# TRV_MRF49_V1_2.net
KiCad netlist of a schematic drawn in EAGLE
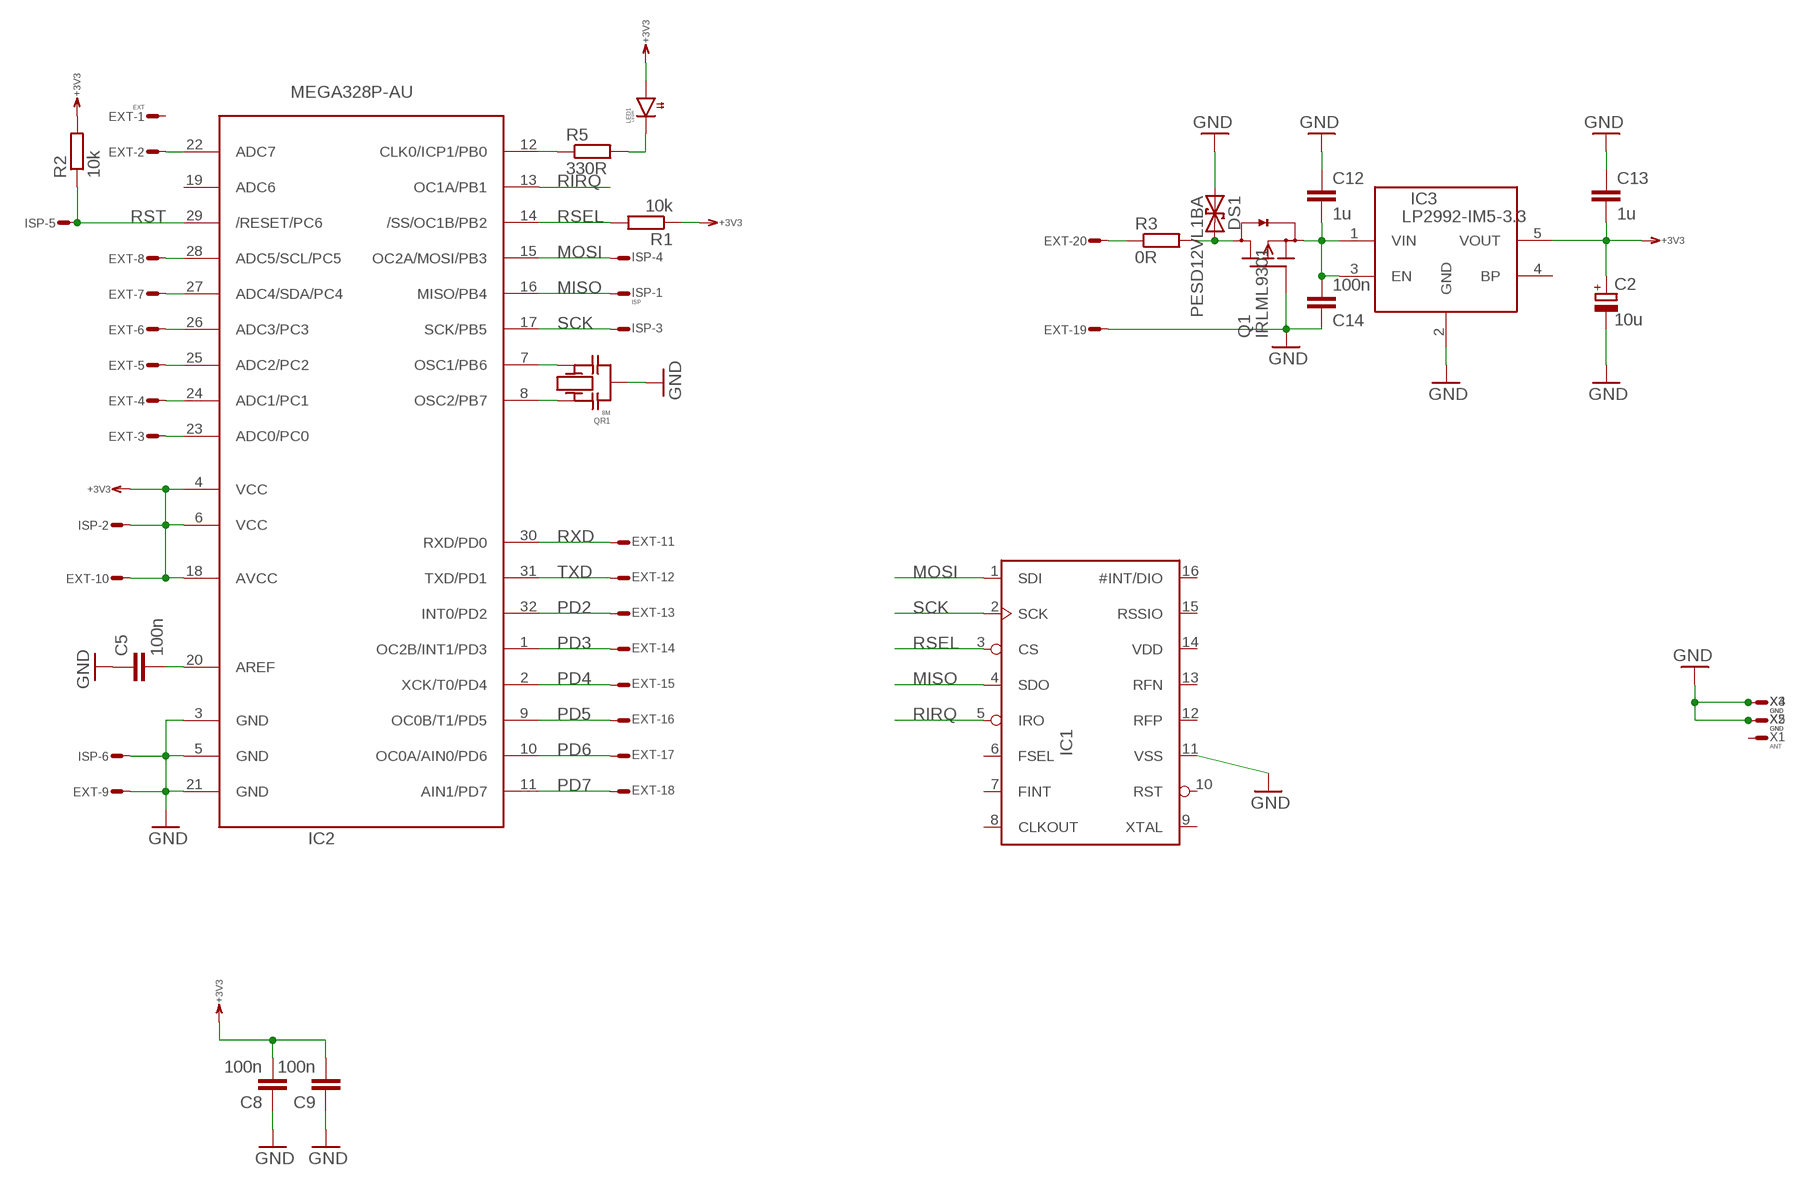
[diagram p0: schematic, sheet 1]

(export (version "E")
  (design (tool "Eeschema 10.0.6"))
  (components
    (comp (ref "C2")
      (value "10u")
      (footprint "eagle-import:SMC_B")
      (libsource (lib "eagle-import") (part "C_POLSMCB"))
    )
    (comp (ref "C5")
      (value "100n")
      (footprint "eagle-import:0603")
      (libsource (lib "eagle-import") (part "C0603"))
    )
    (comp (ref "C8")
      (value "100n")
      (footprint "eagle-import:0603")
      (libsource (lib "eagle-import") (part "C0603"))
    )
    (comp (ref "C9")
      (value "100n")
      (footprint "eagle-import:0603")
      (libsource (lib "eagle-import") (part "C0603"))
    )
    (comp (ref "C12")
      (value "1u")
      (footprint "eagle-import:0603")
      (libsource (lib "eagle-import") (part "C0603"))
    )
    (comp (ref "C13")
      (value "1u")
      (footprint "eagle-import:0603")
      (libsource (lib "eagle-import") (part "C0603"))
    )
    (comp (ref "C14")
      (value "100n")
      (footprint "eagle-import:0603")
      (libsource (lib "eagle-import") (part "C0603"))
    )
    (comp (ref "DS1")
      (value "PESD12VL1BA")
      (footprint "eagle-import:SOD323")
      (libsource (lib "eagle-import") (part "TVS-U323"))
    )
    (comp (ref "EXT")
      (value "EXT")
      (footprint "eagle-import:ML20S")
      (libsource (lib "eagle-import") (part "ML20?ES"))
    )
    (comp (ref "IC1")
      (value "MRF49XA")
      (footprint "eagle-import:TSSOP16")
      (libsource (lib "eagle-import") (part "MRF49XA"))
    )
    (comp (ref "IC2")
      (value "MEGA328P-AU")
      (footprint "eagle-import:TQFP32-08")
      (libsource (lib "eagle-import") (part "MEGA168PA"))
    )
    (comp (ref "IC3")
      (value "LP2992-IM5-3.3")
      (footprint "eagle-import:SOT23-5")
      (libsource (lib "eagle-import") (part "LDO"))
    )
    (comp (ref "ISP")
      (value "ISP")
      (footprint "eagle-import:ML6S")
      (libsource (lib "eagle-import") (part "ML6ES"))
    )
    (comp (ref "LED1")
      (value "LEDR")
      (footprint "eagle-import:0805")
      (libsource (lib "eagle-import") (part "LED0805"))
    )
    (comp (ref "Q1")
      (value "IRLML9301")
      (footprint "eagle-import:SOT23")
      (libsource (lib "eagle-import") (part "FET-PDSOT23"))
    )
    (comp (ref "QR1")
      (value "8M")
      (footprint "eagle-import:CR")
      (libsource (lib "eagle-import") (part "QRCR"))
    )
    (comp (ref "R1")
      (value "10k")
      (footprint "eagle-import:0603")
      (libsource (lib "eagle-import") (part "R0603"))
    )
    (comp (ref "R2")
      (value "10k")
      (footprint "eagle-import:0603")
      (libsource (lib "eagle-import") (part "R0603"))
    )
    (comp (ref "R3")
      (value "0R")
      (footprint "eagle-import:0603")
      (libsource (lib "eagle-import") (part "R0603"))
    )
    (comp (ref "R5")
      (value "330R")
      (footprint "eagle-import:0603")
      (libsource (lib "eagle-import") (part "R0603"))
    )
    (comp (ref "X1")
      (value "ANT")
      (footprint "eagle-import:S2.54_1.27")
      (libsource (lib "eagle-import") (part "WIREPADS2.54/1.27"))
    )
    (comp (ref "X2")
      (value "GND")
      (footprint "eagle-import:S2.54_1.27")
      (libsource (lib "eagle-import") (part "WIREPADS2.54/1.27"))
    )
    (comp (ref "X3")
      (value "GND")
      (footprint "eagle-import:S2.54_1.27")
      (libsource (lib "eagle-import") (part "WIREPADS2.54/1.27"))
    )
    (comp (ref "X4")
      (value "GND")
      (footprint "eagle-import:S2.54_1.27")
      (libsource (lib "eagle-import") (part "WIREPADS2.54/1.27"))
    )
    (comp (ref "X5")
      (value "GND")
      (footprint "eagle-import:S2.54_1.27")
      (libsource (lib "eagle-import") (part "WIREPADS2.54/1.27"))
    )
  )
  (nets
    (net (code "1") (name "+3V3") (class "Default")
      (node (ref "C13") (pin "2") (pinfunction "2_2") (pintype "passive"))
      (node (ref "C2") (pin "+") (pinfunction "+_+") (pintype "passive"))
      (node (ref "C8") (pin "2") (pinfunction "2_2") (pintype "passive"))
      (node (ref "C9") (pin "2") (pinfunction "2_2") (pintype "passive"))
      (node (ref "EXT") (pin "10") (pinfunction "S_10") (pintype "passive"))
      (node (ref "IC2") (pin "18") (pinfunction "AVCC_18") (pintype "bidirectional"))
      (node (ref "IC2") (pin "4") (pinfunction "VCC_4") (pintype "bidirectional"))
      (node (ref "IC2") (pin "6") (pinfunction "VCC_6") (pintype "bidirectional"))
      (node (ref "IC3") (pin "5") (pinfunction "VOUT_5") (pintype "bidirectional"))
      (node (ref "ISP") (pin "2") (pinfunction "S_2") (pintype "passive"))
      (node (ref "LED1") (pin "C") (pinfunction "A_C") (pintype "bidirectional"))
      (node (ref "R1") (pin "1") (pinfunction "1_1") (pintype "passive"))
      (node (ref "R2") (pin "2") (pinfunction "2_2") (pintype "passive"))
    )
    (net (code "2") (name "/MISO") (class "Default")
      (node (ref "IC1") (pin "4") (pinfunction "SDO_4") (pintype "output"))
      (node (ref "IC2") (pin "16") (pinfunction "MISO/PB4_16") (pintype "bidirectional"))
      (node (ref "ISP") (pin "1") (pinfunction "S_1") (pintype "passive"))
    )
    (net (code "3") (name "/MOSI") (class "Default")
      (node (ref "IC1") (pin "1") (pinfunction "SDI_1") (pintype "input"))
      (node (ref "IC2") (pin "15") (pinfunction "OC2A/MOSI/PB3_15") (pintype "bidirectional"))
      (node (ref "ISP") (pin "4") (pinfunction "S_4") (pintype "passive"))
    )
    (net (code "4") (name "/PD2") (class "Default")
      (node (ref "EXT") (pin "13") (pinfunction "S_13") (pintype "passive"))
      (node (ref "IC2") (pin "32") (pinfunction "INT0/PD2_32") (pintype "bidirectional"))
    )
    (net (code "5") (name "/PD3") (class "Default")
      (node (ref "EXT") (pin "14") (pinfunction "S_14") (pintype "passive"))
      (node (ref "IC2") (pin "1") (pinfunction "OC2B/INT1/PD3_1") (pintype "bidirectional"))
    )
    (net (code "6") (name "/PD4") (class "Default")
      (node (ref "EXT") (pin "15") (pinfunction "S_15") (pintype "passive"))
      (node (ref "IC2") (pin "2") (pinfunction "XCK/T0/PD4_2") (pintype "bidirectional"))
    )
    (net (code "7") (name "/PD5") (class "Default")
      (node (ref "EXT") (pin "16") (pinfunction "S_16") (pintype "passive"))
      (node (ref "IC2") (pin "9") (pinfunction "OC0B/T1/PD5_9") (pintype "bidirectional"))
    )
    (net (code "8") (name "/PD6") (class "Default")
      (node (ref "EXT") (pin "17") (pinfunction "S_17") (pintype "passive"))
      (node (ref "IC2") (pin "10") (pinfunction "OC0A/AIN0/PD6_10") (pintype "bidirectional"))
    )
    (net (code "9") (name "/PD7") (class "Default")
      (node (ref "EXT") (pin "18") (pinfunction "S_18") (pintype "passive"))
      (node (ref "IC2") (pin "11") (pinfunction "AIN1/PD7_11") (pintype "bidirectional"))
    )
    (net (code "10") (name "/RIRQ") (class "Default")
      (node (ref "IC1") (pin "5") (pinfunction "IRO_5") (pintype "output"))
      (node (ref "IC2") (pin "13") (pinfunction "OC1A/PB1_13") (pintype "bidirectional"))
    )
    (net (code "11") (name "/RSEL") (class "Default")
      (node (ref "IC1") (pin "3") (pinfunction "CS_3") (pintype "input"))
      (node (ref "IC2") (pin "14") (pinfunction "/SS/OC1B/PB2_14") (pintype "bidirectional"))
      (node (ref "R1") (pin "2") (pinfunction "2_2") (pintype "passive"))
    )
    (net (code "12") (name "/RST") (class "Default")
      (node (ref "IC2") (pin "29") (pinfunction "/RESET/PC6_29") (pintype "bidirectional"))
      (node (ref "ISP") (pin "5") (pinfunction "S_5") (pintype "passive"))
      (node (ref "R2") (pin "1") (pinfunction "1_1") (pintype "passive"))
    )
    (net (code "13") (name "/RXD") (class "Default")
      (node (ref "EXT") (pin "11") (pinfunction "S_11") (pintype "passive"))
      (node (ref "IC2") (pin "30") (pinfunction "RXD/PD0_30") (pintype "bidirectional"))
    )
    (net (code "14") (name "/SCK") (class "Default")
      (node (ref "IC1") (pin "2") (pinfunction "SCK_2") (pintype "input"))
      (node (ref "IC2") (pin "17") (pinfunction "SCK/PB5_17") (pintype "bidirectional"))
      (node (ref "ISP") (pin "3") (pinfunction "S_3") (pintype "passive"))
    )
    (net (code "15") (name "/TXD") (class "Default")
      (node (ref "EXT") (pin "12") (pinfunction "S_12") (pintype "passive"))
      (node (ref "IC2") (pin "31") (pinfunction "TXD/PD1_31") (pintype "bidirectional"))
    )
    (net (code "16") (name "GND") (class "Default")
      (node (ref "C12") (pin "1") (pinfunction "1_1") (pintype "passive"))
      (node (ref "C13") (pin "1") (pinfunction "1_1") (pintype "passive"))
      (node (ref "C14") (pin "1") (pinfunction "1_1") (pintype "passive"))
      (node (ref "C2") (pin "-") (pinfunction "-_-") (pintype "passive"))
      (node (ref "C5") (pin "1") (pinfunction "1_1") (pintype "passive"))
      (node (ref "C8") (pin "1") (pinfunction "1_1") (pintype "passive"))
      (node (ref "C9") (pin "1") (pinfunction "1_1") (pintype "passive"))
      (node (ref "DS1") (pin "A") (pinfunction "1_A") (pintype "passive"))
      (node (ref "EXT") (pin "19") (pinfunction "S_19") (pintype "passive"))
      (node (ref "EXT") (pin "9") (pinfunction "S_9") (pintype "passive"))
      (node (ref "IC1") (pin "11") (pinfunction "VSS_11") (pintype "input"))
      (node (ref "IC2") (pin "21") (pinfunction "GND_21") (pintype "bidirectional"))
      (node (ref "IC2") (pin "3") (pinfunction "GND_3") (pintype "bidirectional"))
      (node (ref "IC2") (pin "5") (pinfunction "GND_5") (pintype "bidirectional"))
      (node (ref "IC3") (pin "2") (pinfunction "GND_2") (pintype "bidirectional"))
      (node (ref "ISP") (pin "6") (pinfunction "S_6") (pintype "passive"))
      (node (ref "Q1") (pin "1") (pinfunction "G_1") (pintype "passive"))
      (node (ref "QR1") (pin "M") (pinfunction "M_M") (pintype "passive"))
      (node (ref "X2") (pin "1") (pinfunction "S_1") (pintype "passive"))
      (node (ref "X3") (pin "1") (pinfunction "S_1") (pintype "passive"))
      (node (ref "X4") (pin "1") (pinfunction "S_1") (pintype "passive"))
      (node (ref "X5") (pin "1") (pinfunction "S_1") (pintype "passive"))
    )
    (net (code "17") (name "Net-(DS1-2)") (class "Default")
      (node (ref "DS1") (pin "C") (pinfunction "2_C") (pintype "passive"))
      (node (ref "Q1") (pin "3") (pinfunction "D_3") (pintype "passive"))
      (node (ref "R3") (pin "2") (pinfunction "2_2") (pintype "passive"))
    )
    (net (code "18") (name "Net-(EXTL-S)") (class "Default")
      (node (ref "EXT") (pin "2") (pinfunction "S_2") (pintype "passive"))
      (node (ref "IC2") (pin "22") (pinfunction "ADC7_22") (pintype "bidirectional"))
    )
    (net (code "19") (name "Net-(EXTM-S)") (class "Default")
      (node (ref "EXT") (pin "20") (pinfunction "S_20") (pintype "passive"))
      (node (ref "R3") (pin "1") (pinfunction "1_1") (pintype "passive"))
    )
    (net (code "20") (name "Net-(EXTN-S)") (class "Default")
      (node (ref "EXT") (pin "3") (pinfunction "S_3") (pintype "passive"))
      (node (ref "IC2") (pin "23") (pinfunction "ADC0/PC0_23") (pintype "bidirectional"))
    )
    (net (code "21") (name "Net-(EXTO-S)") (class "Default")
      (node (ref "EXT") (pin "4") (pinfunction "S_4") (pintype "passive"))
      (node (ref "IC2") (pin "24") (pinfunction "ADC1/PC1_24") (pintype "bidirectional"))
    )
    (net (code "22") (name "Net-(EXTP-S)") (class "Default")
      (node (ref "EXT") (pin "5") (pinfunction "S_5") (pintype "passive"))
      (node (ref "IC2") (pin "25") (pinfunction "ADC2/PC2_25") (pintype "bidirectional"))
    )
    (net (code "23") (name "Net-(EXTQ-S)") (class "Default")
      (node (ref "EXT") (pin "6") (pinfunction "S_6") (pintype "passive"))
      (node (ref "IC2") (pin "26") (pinfunction "ADC3/PC3_26") (pintype "bidirectional"))
    )
    (net (code "24") (name "Net-(EXTR-S)") (class "Default")
      (node (ref "EXT") (pin "7") (pinfunction "S_7") (pintype "passive"))
      (node (ref "IC2") (pin "27") (pinfunction "ADC4/SDA/PC4_27") (pintype "bidirectional"))
    )
    (net (code "25") (name "Net-(EXTS-S)") (class "Default")
      (node (ref "EXT") (pin "8") (pinfunction "S_8") (pintype "passive"))
      (node (ref "IC2") (pin "28") (pinfunction "ADC5/SCL/PC5_28") (pintype "bidirectional"))
    )
    (net (code "26") (name "Net-(IC2-AREF)") (class "Default")
      (node (ref "C5") (pin "2") (pinfunction "2_2") (pintype "passive"))
      (node (ref "IC2") (pin "20") (pinfunction "AREF_20") (pintype "bidirectional"))
    )
    (net (code "27") (name "Net-(IC2-CLK0{slash}ICP1{slash}PB0)") (class "Default")
      (node (ref "IC2") (pin "12") (pinfunction "CLK0/ICP1/PB0_12") (pintype "bidirectional"))
      (node (ref "R5") (pin "1") (pinfunction "1_1") (pintype "passive"))
    )
    (net (code "28") (name "Net-(IC2-OSC1{slash}PB6)") (class "Default")
      (node (ref "IC2") (pin "7") (pinfunction "OSC1/PB6_7") (pintype "bidirectional"))
      (node (ref "QR1") (pin "2") (pinfunction "2_2") (pintype "passive"))
    )
    (net (code "29") (name "Net-(IC2-OSC2{slash}PB7)") (class "Default")
      (node (ref "IC2") (pin "8") (pinfunction "OSC2/PB7_8") (pintype "bidirectional"))
      (node (ref "QR1") (pin "1") (pinfunction "1_1") (pintype "passive"))
    )
    (net (code "30") (name "Net-(IC3-EN)") (class "Default")
      (node (ref "C12") (pin "2") (pinfunction "2_2") (pintype "passive"))
      (node (ref "C14") (pin "2") (pinfunction "2_2") (pintype "passive"))
      (node (ref "IC3") (pin "1") (pinfunction "VIN_1") (pintype "bidirectional"))
      (node (ref "IC3") (pin "3") (pinfunction "EN_3") (pintype "bidirectional"))
      (node (ref "Q1") (pin "2") (pinfunction "S_2") (pintype "passive"))
    )
    (net (code "31") (name "Net-(LED1-C)") (class "Default")
      (node (ref "LED1") (pin "A") (pinfunction "C_A") (pintype "bidirectional"))
      (node (ref "R5") (pin "2") (pinfunction "2_2") (pintype "passive"))
    )
    (net (code "32") (name "unconnected-(EXTA-S-Pad1)") (class "Default")
      (node (ref "EXT") (pin "1") (pinfunction "S_1") (pintype "passive"))
    )
    (net (code "33") (name "unconnected-(IC1-#INT{slash}DIO-Pad16)") (class "Default")
      (node (ref "IC1") (pin "16") (pinfunction "#INT/DIO_16") (pintype "bidirectional"))
    )
    (net (code "34") (name "unconnected-(IC1-CLKOUT-Pad8)") (class "Default")
      (node (ref "IC1") (pin "8") (pinfunction "CLKOUT_8") (pintype "output"))
    )
    (net (code "35") (name "unconnected-(IC1-FINT-Pad7)") (class "Default")
      (node (ref "IC1") (pin "7") (pinfunction "FINT_7") (pintype "bidirectional"))
    )
    (net (code "36") (name "unconnected-(IC1-FSEL-Pad6)") (class "Default")
      (node (ref "IC1") (pin "6") (pinfunction "FSEL_6") (pintype "bidirectional"))
    )
    (net (code "37") (name "unconnected-(IC1-RFN-Pad13)") (class "Default")
      (node (ref "IC1") (pin "13") (pinfunction "RFN_13") (pintype "bidirectional"))
    )
    (net (code "38") (name "unconnected-(IC1-RFP-Pad12)") (class "Default")
      (node (ref "IC1") (pin "12") (pinfunction "RFP_12") (pintype "bidirectional"))
    )
    (net (code "39") (name "unconnected-(IC1-RSSIO-Pad15)") (class "Default")
      (node (ref "IC1") (pin "15") (pinfunction "RSSIO_15") (pintype "bidirectional"))
    )
    (net (code "40") (name "unconnected-(IC1-RST-Pad10)") (class "Default")
      (node (ref "IC1") (pin "10") (pinfunction "RST_10") (pintype "bidirectional"))
    )
    (net (code "41") (name "unconnected-(IC1-VDD-Pad14)") (class "Default")
      (node (ref "IC1") (pin "14") (pinfunction "VDD_14") (pintype "input"))
    )
    (net (code "42") (name "unconnected-(IC1-XTAL-Pad9)") (class "Default")
      (node (ref "IC1") (pin "9") (pinfunction "XTAL_9") (pintype "input"))
    )
    (net (code "43") (name "unconnected-(IC2-ADC6-Pad19)") (class "Default")
      (node (ref "IC2") (pin "19") (pinfunction "ADC6_19") (pintype "bidirectional"))
    )
    (net (code "44") (name "unconnected-(IC3-BP-Pad4)") (class "Default")
      (node (ref "IC3") (pin "4") (pinfunction "BP_4") (pintype "bidirectional"))
    )
    (net (code "45") (name "unconnected-(X1-S-Pad1)") (class "Default")
      (node (ref "X1") (pin "1") (pinfunction "S_1") (pintype "passive"))
    )
  )
)
